# HX711_Sparkfun.net
KiCad netlist of a schematic drawn in EAGLE
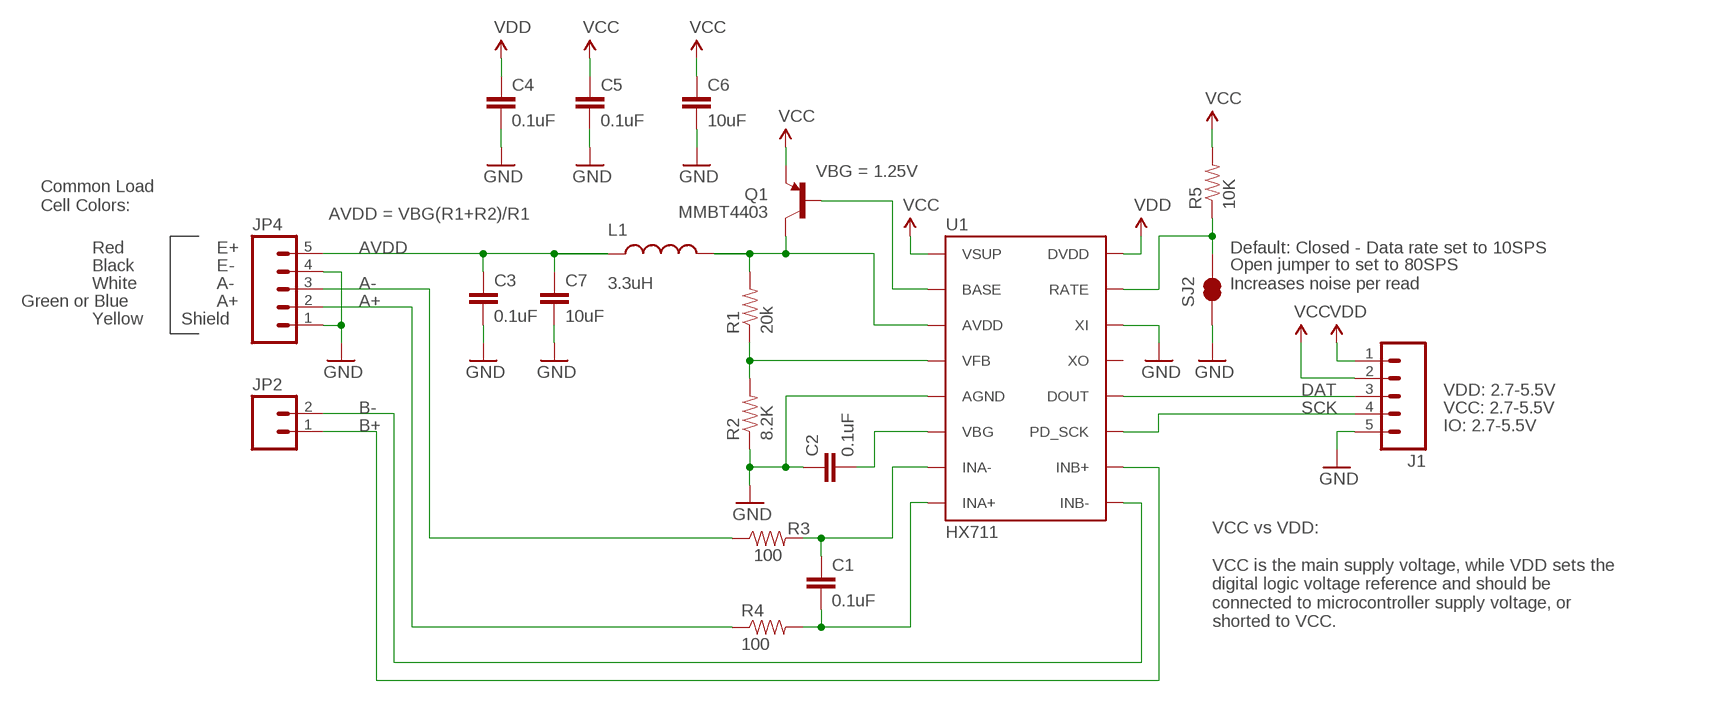
[diagram p0: schematic, sheet 1]

(export (version "E")
  (design (tool "Eeschema 10.0.6"))
  (components
    (comp (ref "C1")
      (value "0.1uF")
      (footprint "eagle-import:0603-CAP")
      (libsource (lib "eagle-import") (part "0.1UF-25V-5%(0603)"))
    )
    (comp (ref "C2")
      (value "0.1uF")
      (footprint "eagle-import:0603-CAP")
      (libsource (lib "eagle-import") (part "0.1UF-25V-5%(0603)"))
    )
    (comp (ref "C3")
      (value "0.1uF")
      (footprint "eagle-import:0603-CAP")
      (libsource (lib "eagle-import") (part "0.1UF-25V-5%(0603)"))
    )
    (comp (ref "C4")
      (value "0.1uF")
      (footprint "eagle-import:0603-CAP")
      (libsource (lib "eagle-import") (part "0.1UF-25V-5%(0603)"))
    )
    (comp (ref "C5")
      (value "0.1uF")
      (footprint "eagle-import:0603-CAP")
      (libsource (lib "eagle-import") (part "0.1UF-25V-5%(0603)"))
    )
    (comp (ref "C6")
      (value "10uF")
      (footprint "eagle-import:1210")
      (libsource (lib "eagle-import") (part "10UF50V20%(1210)"))
    )
    (comp (ref "C7")
      (value "10uF")
      (footprint "eagle-import:1210")
      (libsource (lib "eagle-import") (part "10UF50V20%(1210)"))
    )
    (comp (ref "J1")
      (value "M05PTH")
      (footprint "eagle-import:1X05")
      (libsource (lib "eagle-import") (part "M05PTH"))
    )
    (comp (ref "JP2")
      (value "M02PTH")
      (footprint "eagle-import:1X02")
      (libsource (lib "eagle-import") (part "M02PTH"))
    )
    (comp (ref "JP4")
      (value "M05PTH")
      (footprint "eagle-import:1X05")
      (libsource (lib "eagle-import") (part "M05PTH"))
    )
    (comp (ref "L1")
      (value "3.3uH")
      (footprint "eagle-import:0805")
      (libsource (lib "eagle-import") (part "INDUCTOR0805-IND"))
    )
    (comp (ref "Q1")
      (value "MMBT4403")
      (footprint "eagle-import:SOT23-3")
      (libsource (lib "eagle-import") (part "TRANSISTOR_PNPMMBT4403"))
    )
    (comp (ref "R1")
      (value "20k")
      (footprint "eagle-import:0603-RES")
      (libsource (lib "eagle-import") (part "20KOHM1/10W1%(0603)"))
    )
    (comp (ref "R2")
      (value "8.2K")
      (footprint "eagle-import:0603-RES")
      (libsource (lib "eagle-import") (part "8.2KOHM-1/10W-5%(0603)"))
    )
    (comp (ref "R3")
      (value "100")
      (footprint "eagle-import:0603-RES")
      (libsource (lib "eagle-import") (part "100OHM-1/10W-1%(0603)"))
    )
    (comp (ref "R4")
      (value "100")
      (footprint "eagle-import:0603-RES")
      (libsource (lib "eagle-import") (part "100OHM-1/10W-1%(0603)"))
    )
    (comp (ref "R5")
      (value "10K")
      (footprint "eagle-import:0603-RES")
      (libsource (lib "eagle-import") (part "10KOHM-1/10W-1%(0603)0603"))
    )
    (comp (ref "SJ2")
      (value "JUMPER-PAD-2-NC_BY_TRACE")
      (footprint "eagle-import:PAD-JUMPER-2-NC_BY_TRACE_YES_SILK")
      (libsource (lib "eagle-import") (part "JUMPER-PAD-2-NC_BY_TRACE"))
    )
    (comp (ref "U1")
      (value "HX711")
      (footprint "eagle-import:SO16")
      (libsource (lib "eagle-import") (part "HX711HX711"))
    )
  )
  (nets
    (net (code "1") (name "/A+") (class "Default")
      (node (ref "JP4") (pin "2") (pinfunction "2_2") (pintype "passive"))
      (node (ref "R4") (pin "1") (pinfunction "1_1") (pintype "passive"))
    )
    (net (code "2") (name "/A-") (class "Default")
      (node (ref "JP4") (pin "3") (pinfunction "3_3") (pintype "passive"))
      (node (ref "R3") (pin "1") (pinfunction "1_1") (pintype "passive"))
    )
    (net (code "3") (name "/AVDD") (class "Default")
      (node (ref "C3") (pin "1") (pinfunction "1_1") (pintype "passive"))
      (node (ref "C7") (pin "1") (pinfunction "1_1") (pintype "passive"))
      (node (ref "JP4") (pin "5") (pinfunction "5_5") (pintype "passive"))
      (node (ref "L1") (pin "1") (pinfunction "1_1") (pintype "passive"))
    )
    (net (code "4") (name "/B+") (class "Default")
      (node (ref "JP2") (pin "1") (pinfunction "1_1") (pintype "passive"))
      (node (ref "U1") (pin "10") (pinfunction "INB+_10") (pintype "bidirectional"))
    )
    (net (code "5") (name "/B-") (class "Default")
      (node (ref "JP2") (pin "2") (pinfunction "2_2") (pintype "passive"))
      (node (ref "U1") (pin "9") (pinfunction "INB-_9") (pintype "bidirectional"))
    )
    (net (code "6") (name "/DAT") (class "Default")
      (node (ref "J1") (pin "3") (pinfunction "3_3") (pintype "passive"))
      (node (ref "U1") (pin "12") (pinfunction "DOUT_12") (pintype "bidirectional"))
    )
    (net (code "7") (name "/SCK") (class "Default")
      (node (ref "J1") (pin "4") (pinfunction "4_4") (pintype "passive"))
      (node (ref "U1") (pin "11") (pinfunction "PD_SCK_11") (pintype "bidirectional"))
    )
    (net (code "8") (name "GND") (class "Default")
      (node (ref "C2") (pin "1") (pinfunction "1_1") (pintype "passive"))
      (node (ref "C3") (pin "2") (pinfunction "2_2") (pintype "passive"))
      (node (ref "C4") (pin "2") (pinfunction "2_2") (pintype "passive"))
      (node (ref "C5") (pin "2") (pinfunction "2_2") (pintype "passive"))
      (node (ref "C6") (pin "2") (pinfunction "2_2") (pintype "passive"))
      (node (ref "C7") (pin "2") (pinfunction "2_2") (pintype "passive"))
      (node (ref "J1") (pin "5") (pinfunction "5_5") (pintype "passive"))
      (node (ref "JP4") (pin "1") (pinfunction "1_1") (pintype "passive"))
      (node (ref "JP4") (pin "4") (pinfunction "4_4") (pintype "passive"))
      (node (ref "R2") (pin "1") (pinfunction "1_1") (pintype "passive"))
      (node (ref "SJ2") (pin "1") (pinfunction "1_1") (pintype "passive"))
      (node (ref "U1") (pin "14") (pinfunction "XI_14") (pintype "bidirectional"))
      (node (ref "U1") (pin "5") (pinfunction "AGND_5") (pintype "bidirectional"))
    )
    (net (code "9") (name "Net-(Q1-B)") (class "Default")
      (node (ref "Q1") (pin "1") (pinfunction "B_1") (pintype "passive"))
      (node (ref "U1") (pin "2") (pinfunction "BASE_2") (pintype "bidirectional"))
    )
    (net (code "10") (name "Net-(Q1-C)") (class "Default")
      (node (ref "L1") (pin "2") (pinfunction "2_2") (pintype "passive"))
      (node (ref "Q1") (pin "3") (pinfunction "C_3") (pintype "passive"))
      (node (ref "R1") (pin "2") (pinfunction "2_2") (pintype "passive"))
      (node (ref "U1") (pin "3") (pinfunction "AVDD_3") (pintype "bidirectional"))
    )
    (net (code "11") (name "Net-(U1-INA+)") (class "Default")
      (node (ref "C1") (pin "2") (pinfunction "2_2") (pintype "passive"))
      (node (ref "R4") (pin "2") (pinfunction "2_2") (pintype "passive"))
      (node (ref "U1") (pin "8") (pinfunction "INA+_8") (pintype "bidirectional"))
    )
    (net (code "12") (name "Net-(U1-INA-)") (class "Default")
      (node (ref "C1") (pin "1") (pinfunction "1_1") (pintype "passive"))
      (node (ref "R3") (pin "2") (pinfunction "2_2") (pintype "passive"))
      (node (ref "U1") (pin "7") (pinfunction "INA-_7") (pintype "bidirectional"))
    )
    (net (code "13") (name "Net-(U1-RATE)") (class "Default")
      (node (ref "R5") (pin "1") (pinfunction "1_1") (pintype "passive"))
      (node (ref "SJ2") (pin "2") (pinfunction "2_2") (pintype "passive"))
      (node (ref "U1") (pin "15") (pinfunction "RATE_15") (pintype "bidirectional"))
    )
    (net (code "14") (name "Net-(U1-VBG)") (class "Default")
      (node (ref "C2") (pin "2") (pinfunction "2_2") (pintype "passive"))
      (node (ref "U1") (pin "6") (pinfunction "VBG_6") (pintype "bidirectional"))
    )
    (net (code "15") (name "Net-(U1-VFB)") (class "Default")
      (node (ref "R1") (pin "1") (pinfunction "1_1") (pintype "passive"))
      (node (ref "R2") (pin "2") (pinfunction "2_2") (pintype "passive"))
      (node (ref "U1") (pin "4") (pinfunction "VFB_4") (pintype "bidirectional"))
    )
    (net (code "16") (name "VCC") (class "Default")
      (node (ref "C5") (pin "1") (pinfunction "1_1") (pintype "passive"))
      (node (ref "C6") (pin "1") (pinfunction "1_1") (pintype "passive"))
      (node (ref "J1") (pin "2") (pinfunction "2_2") (pintype "passive"))
      (node (ref "Q1") (pin "2") (pinfunction "E_2") (pintype "passive"))
      (node (ref "R5") (pin "2") (pinfunction "2_2") (pintype "passive"))
      (node (ref "U1") (pin "1") (pinfunction "VSUP_1") (pintype "bidirectional"))
    )
    (net (code "17") (name "VDD") (class "Default")
      (node (ref "C4") (pin "1") (pinfunction "1_1") (pintype "passive"))
      (node (ref "J1") (pin "1") (pinfunction "1_1") (pintype "passive"))
      (node (ref "U1") (pin "16") (pinfunction "DVDD_16") (pintype "bidirectional"))
    )
    (net (code "18") (name "unconnected-(U1-XO-Pad13)") (class "Default")
      (node (ref "U1") (pin "13") (pinfunction "XO_13") (pintype "bidirectional"))
    )
  )
)
